# oled_watch_ver2_3.net
KiCad netlist of a schematic drawn in EAGLE
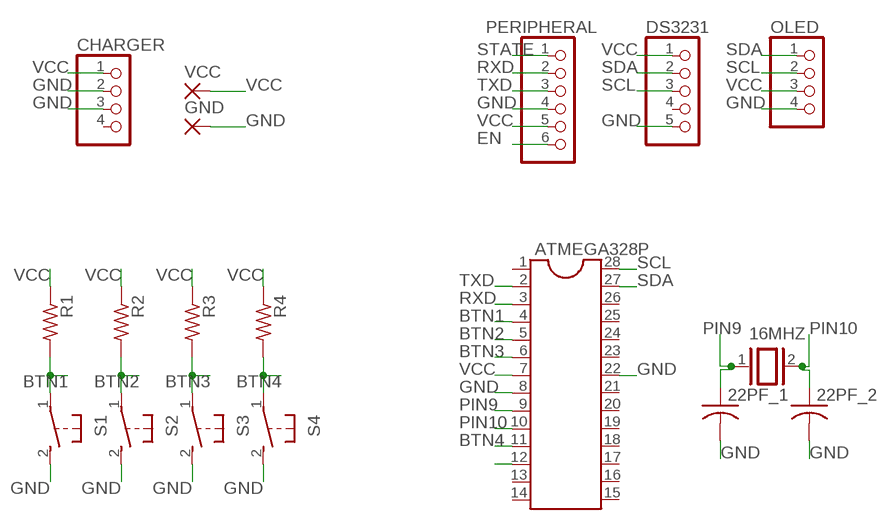
[diagram p0: schematic, sheet 1]

(export (version "E")
  (design (tool "Eeschema 10.0.6"))
  (components
    (comp (ref "16MHZ")
      (value "XTAL/S")
      (footprint "eagle-import:QS")
      (libsource (lib "eagle-import") (part "XTAL/S"))
    )
    (comp (ref "22PF_1")
      (value "C-US025-024X044")
      (footprint "eagle-import:C025-024X044")
      (libsource (lib "eagle-import") (part "C-US025-024X044"))
    )
    (comp (ref "22PF_2")
      (value "C-US025-024X044")
      (footprint "eagle-import:C025-024X044")
      (libsource (lib "eagle-import") (part "C-US025-024X044"))
    )
    (comp (ref "ATMEGA328P")
      (value "DIL28-3")
      (footprint "eagle-import:DIL28-3")
      (libsource (lib "eagle-import") (part "DIL28-3"))
    )
    (comp (ref "CHARGER")
      (value "PINHD-1X4")
      (footprint "eagle-import:1X04")
      (libsource (lib "eagle-import") (part "PINHD-1X4"))
    )
    (comp (ref "DS3231")
      (value "PINHD-1X5")
      (footprint "eagle-import:1X05")
      (libsource (lib "eagle-import") (part "PINHD-1X5"))
    )
    (comp (ref "GND")
      (value "2,54/0,8")
      (footprint "eagle-import:2,54_0,8")
      (libsource (lib "eagle-import") (part "2,54/0,8"))
    )
    (comp (ref "OLED")
      (value "PINHD-1X4")
      (footprint "eagle-import:1X04")
      (libsource (lib "eagle-import") (part "PINHD-1X4"))
    )
    (comp (ref "PERIPHERAL")
      (value "PINHD-1X6")
      (footprint "eagle-import:1X06")
      (libsource (lib "eagle-import") (part "PINHD-1X6"))
    )
    (comp (ref "R1")
      (value "R-US_0207/7")
      (footprint "eagle-import:0207_7")
      (libsource (lib "eagle-import") (part "R-US_0207/7"))
    )
    (comp (ref "R2")
      (value "R-US_0207/7")
      (footprint "eagle-import:0207_7")
      (libsource (lib "eagle-import") (part "R-US_0207/7"))
    )
    (comp (ref "R3")
      (value "R-US_0207/7")
      (footprint "eagle-import:0207_7")
      (libsource (lib "eagle-import") (part "R-US_0207/7"))
    )
    (comp (ref "R4")
      (value "R-US_0207/7")
      (footprint "eagle-import:0207_7")
      (libsource (lib "eagle-import") (part "R-US_0207/7"))
    )
    (comp (ref "S1")
      (value "31-XX")
      (footprint "eagle-import:B3F-31XX")
      (fields (field (name "MPN") "B3F-3100"))
      (libsource (lib "eagle-import") (part "31-XX"))
    )
    (comp (ref "S2")
      (value "31-XX")
      (footprint "eagle-import:B3F-31XX")
      (fields (field (name "MPN") "B3F-3100"))
      (libsource (lib "eagle-import") (part "31-XX"))
    )
    (comp (ref "S3")
      (value "31-XX")
      (footprint "eagle-import:B3F-31XX")
      (fields (field (name "MPN") "B3F-3100"))
      (libsource (lib "eagle-import") (part "31-XX"))
    )
    (comp (ref "S4")
      (value "31-XX")
      (footprint "eagle-import:B3F-31XX")
      (fields (field (name "MPN") "B3F-3100"))
      (libsource (lib "eagle-import") (part "31-XX"))
    )
    (comp (ref "VCC")
      (value "2,54/0,8")
      (footprint "eagle-import:2,54_0,8")
      (libsource (lib "eagle-import") (part "2,54/0,8"))
    )
  )
  (nets
    (net (code "1") (name "/BTN1") (class "Default")
      (node (ref "ATMEGA328P") (pin "4") (pinfunction "4_4") (pintype "passive"))
      (node (ref "R1") (pin "2") (pinfunction "2_2") (pintype "passive"))
      (node (ref "S1") (pin "1") (pinfunction "P_1") (pintype "passive"))
    )
    (net (code "2") (name "/BTN2") (class "Default")
      (node (ref "ATMEGA328P") (pin "5") (pinfunction "5_5") (pintype "passive"))
      (node (ref "R2") (pin "2") (pinfunction "2_2") (pintype "passive"))
      (node (ref "S2") (pin "1") (pinfunction "P_1") (pintype "passive"))
    )
    (net (code "3") (name "/BTN3") (class "Default")
      (node (ref "ATMEGA328P") (pin "6") (pinfunction "6_6") (pintype "passive"))
      (node (ref "R3") (pin "2") (pinfunction "2_2") (pintype "passive"))
      (node (ref "S3") (pin "1") (pinfunction "P_1") (pintype "passive"))
    )
    (net (code "4") (name "/BTN4") (class "Default")
      (node (ref "ATMEGA328P") (pin "11") (pinfunction "11_11") (pintype "passive"))
      (node (ref "R4") (pin "2") (pinfunction "2_2") (pintype "passive"))
      (node (ref "S4") (pin "1") (pinfunction "P_1") (pintype "passive"))
    )
    (net (code "5") (name "/EN") (class "Default")
      (node (ref "PERIPHERAL") (pin "6") (pinfunction "6_6") (pintype "passive"))
    )
    (net (code "6") (name "/GND") (class "Default")
      (node (ref "22PF_1") (pin "2") (pinfunction "2_2") (pintype "passive"))
      (node (ref "22PF_2") (pin "2") (pinfunction "2_2") (pintype "passive"))
      (node (ref "ATMEGA328P") (pin "22") (pinfunction "22_22") (pintype "passive"))
      (node (ref "ATMEGA328P") (pin "8") (pinfunction "8_8") (pintype "passive"))
      (node (ref "CHARGER") (pin "2") (pinfunction "2_2") (pintype "passive"))
      (node (ref "CHARGER") (pin "3") (pinfunction "3_3") (pintype "passive"))
      (node (ref "DS3231") (pin "5") (pinfunction "5_5") (pintype "passive"))
      (node (ref "GND") (pin "1") (pinfunction "P_1") (pintype "passive"))
      (node (ref "OLED") (pin "4") (pinfunction "4_4") (pintype "passive"))
      (node (ref "PERIPHERAL") (pin "4") (pinfunction "4_4") (pintype "passive"))
      (node (ref "S1") (pin "2") (pinfunction "S_2") (pintype "passive"))
      (node (ref "S2") (pin "2") (pinfunction "S_2") (pintype "passive"))
      (node (ref "S3") (pin "2") (pinfunction "S_2") (pintype "passive"))
      (node (ref "S4") (pin "2") (pinfunction "S_2") (pintype "passive"))
    )
    (net (code "7") (name "/PIN9") (class "Default")
      (node (ref "16MHZ") (pin "1") (pinfunction "1_1") (pintype "passive"))
      (node (ref "22PF_1") (pin "1") (pinfunction "1_1") (pintype "passive"))
      (node (ref "ATMEGA328P") (pin "9") (pinfunction "9_9") (pintype "passive"))
    )
    (net (code "8") (name "/PIN10") (class "Default")
      (node (ref "16MHZ") (pin "2") (pinfunction "2_2") (pintype "passive"))
      (node (ref "22PF_2") (pin "1") (pinfunction "1_1") (pintype "passive"))
      (node (ref "ATMEGA328P") (pin "10") (pinfunction "10_10") (pintype "passive"))
    )
    (net (code "9") (name "/RXD") (class "Default")
      (node (ref "ATMEGA328P") (pin "3") (pinfunction "3_3") (pintype "passive"))
      (node (ref "PERIPHERAL") (pin "2") (pinfunction "2_2") (pintype "passive"))
    )
    (net (code "10") (name "/SCL") (class "Default")
      (node (ref "ATMEGA328P") (pin "28") (pinfunction "28_28") (pintype "passive"))
      (node (ref "DS3231") (pin "3") (pinfunction "3_3") (pintype "passive"))
      (node (ref "OLED") (pin "2") (pinfunction "2_2") (pintype "passive"))
    )
    (net (code "11") (name "/SDA") (class "Default")
      (node (ref "ATMEGA328P") (pin "27") (pinfunction "27_27") (pintype "passive"))
      (node (ref "DS3231") (pin "2") (pinfunction "2_2") (pintype "passive"))
      (node (ref "OLED") (pin "1") (pinfunction "1_1") (pintype "passive"))
    )
    (net (code "12") (name "/STATE") (class "Default")
      (node (ref "PERIPHERAL") (pin "1") (pinfunction "1_1") (pintype "passive"))
    )
    (net (code "13") (name "/TXD") (class "Default")
      (node (ref "ATMEGA328P") (pin "2") (pinfunction "2_2") (pintype "passive"))
      (node (ref "PERIPHERAL") (pin "3") (pinfunction "3_3") (pintype "passive"))
    )
    (net (code "14") (name "/VCC") (class "Default")
      (node (ref "ATMEGA328P") (pin "7") (pinfunction "7_7") (pintype "passive"))
      (node (ref "CHARGER") (pin "1") (pinfunction "1_1") (pintype "passive"))
      (node (ref "DS3231") (pin "1") (pinfunction "1_1") (pintype "passive"))
      (node (ref "OLED") (pin "3") (pinfunction "3_3") (pintype "passive"))
      (node (ref "PERIPHERAL") (pin "5") (pinfunction "5_5") (pintype "passive"))
      (node (ref "R1") (pin "1") (pinfunction "1_1") (pintype "passive"))
      (node (ref "R2") (pin "1") (pinfunction "1_1") (pintype "passive"))
      (node (ref "R3") (pin "1") (pinfunction "1_1") (pintype "passive"))
      (node (ref "R4") (pin "1") (pinfunction "1_1") (pintype "passive"))
      (node (ref "VCC") (pin "1") (pinfunction "P_1") (pintype "passive"))
    )
    (net (code "15") (name "unconnected-(ATMEGA328P-Pad1)") (class "Default")
      (node (ref "ATMEGA328P") (pin "1") (pinfunction "1_1") (pintype "passive"))
    )
    (net (code "16") (name "unconnected-(ATMEGA328P-Pad12)") (class "Default")
      (node (ref "ATMEGA328P") (pin "12") (pinfunction "12_12") (pintype "passive"))
    )
    (net (code "17") (name "unconnected-(ATMEGA328P-Pad13)") (class "Default")
      (node (ref "ATMEGA328P") (pin "13") (pinfunction "13_13") (pintype "passive"))
    )
    (net (code "18") (name "unconnected-(ATMEGA328P-Pad14)") (class "Default")
      (node (ref "ATMEGA328P") (pin "14") (pinfunction "14_14") (pintype "passive"))
    )
    (net (code "19") (name "unconnected-(ATMEGA328P-Pad15)") (class "Default")
      (node (ref "ATMEGA328P") (pin "15") (pinfunction "15_15") (pintype "passive"))
    )
    (net (code "20") (name "unconnected-(ATMEGA328P-Pad16)") (class "Default")
      (node (ref "ATMEGA328P") (pin "16") (pinfunction "16_16") (pintype "passive"))
    )
    (net (code "21") (name "unconnected-(ATMEGA328P-Pad17)") (class "Default")
      (node (ref "ATMEGA328P") (pin "17") (pinfunction "17_17") (pintype "passive"))
    )
    (net (code "22") (name "unconnected-(ATMEGA328P-Pad18)") (class "Default")
      (node (ref "ATMEGA328P") (pin "18") (pinfunction "18_18") (pintype "passive"))
    )
    (net (code "23") (name "unconnected-(ATMEGA328P-Pad19)") (class "Default")
      (node (ref "ATMEGA328P") (pin "19") (pinfunction "19_19") (pintype "passive"))
    )
    (net (code "24") (name "unconnected-(ATMEGA328P-Pad20)") (class "Default")
      (node (ref "ATMEGA328P") (pin "20") (pinfunction "20_20") (pintype "passive"))
    )
    (net (code "25") (name "unconnected-(ATMEGA328P-Pad21)") (class "Default")
      (node (ref "ATMEGA328P") (pin "21") (pinfunction "21_21") (pintype "passive"))
    )
    (net (code "26") (name "unconnected-(ATMEGA328P-Pad23)") (class "Default")
      (node (ref "ATMEGA328P") (pin "23") (pinfunction "23_23") (pintype "passive"))
    )
    (net (code "27") (name "unconnected-(ATMEGA328P-Pad24)") (class "Default")
      (node (ref "ATMEGA328P") (pin "24") (pinfunction "24_24") (pintype "passive"))
    )
    (net (code "28") (name "unconnected-(ATMEGA328P-Pad25)") (class "Default")
      (node (ref "ATMEGA328P") (pin "25") (pinfunction "25_25") (pintype "passive"))
    )
    (net (code "29") (name "unconnected-(ATMEGA328P-Pad26)") (class "Default")
      (node (ref "ATMEGA328P") (pin "26") (pinfunction "26_26") (pintype "passive"))
    )
    (net (code "30") (name "unconnected-(CHARGER-Pad4)") (class "Default")
      (node (ref "CHARGER") (pin "4") (pinfunction "4_4") (pintype "passive"))
    )
    (net (code "31") (name "unconnected-(DS3231-Pad4)") (class "Default")
      (node (ref "DS3231") (pin "4") (pinfunction "4_4") (pintype "passive"))
    )
  )
)
